# 19-Power-P5V.net
KiCad netlist of a schematic drawn in Altium Designer
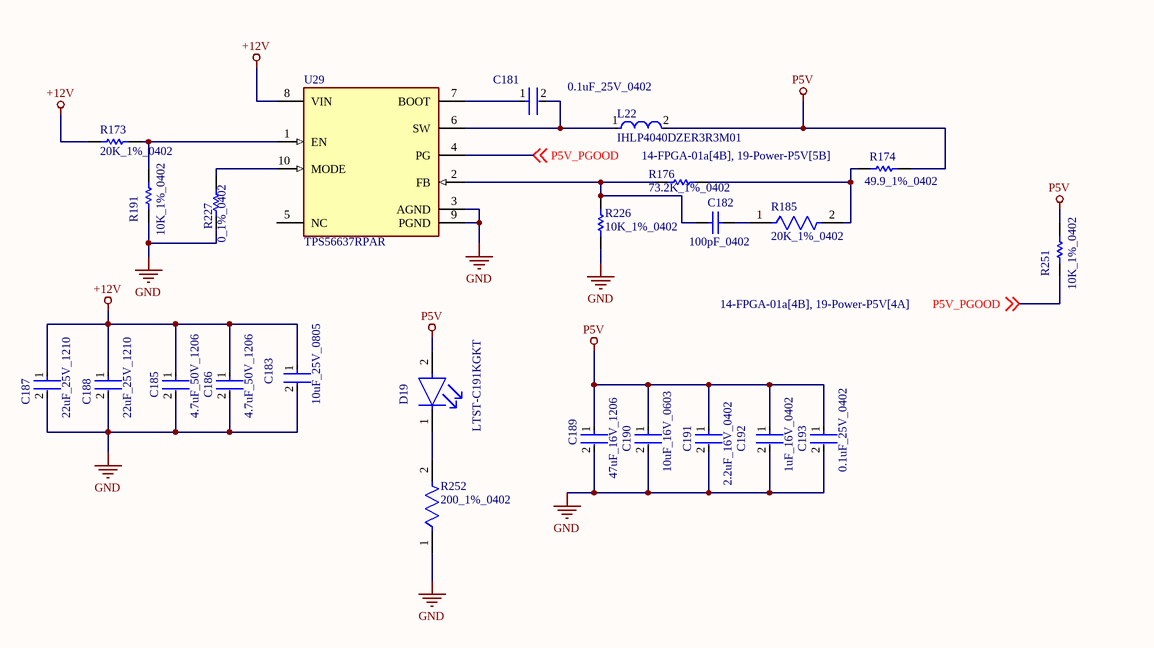
[diagram p0: 19-Power-P5V.SchDoc]

(export (version "E")
  (design (tool "Eeschema 10.0.6"))
  (components
    (comp (ref "C181")
      (value "0.1uF_25V_0402")
      (footprint "FP-0402-L_1_0_1-W_0_5_0_1-IPC_C")
      (description "General Purpose Ceramic Capacitor, 0402, 100nF, 10%, X7R, 15%, 25V")
      (fields (field (name "VOLTAGE") "25V") (field (name "TOLERANCE") "10%"))
      (libsource (lib "Altium Content Vault") (part "b4654b650e69147ec39a6b967a45e02"))
    )
    (comp (ref "C182")
      (value "100pF_0402")
      (footprint "CAPC1005X55X25ML05T10")
      (fields (field (name "MANUFACTURER") "Murata") (field (name "PART NUMBER") "GRM1555C1H101JA01D"))
      (libsource (lib "Altium Content Vault") (part "CAP"))
    )
    (comp (ref "C183")
      (value "10uF_25V_0805")
      (footprint "FP-0805-L_2_0_0_2-W_1_25-MFG")
      (description "Multilayer Ceramic Capacitor 10uF 25V X5R 10% SMD 0805 T/R")
      (fields (field (name "VOLTAGE") "16V") (field (name "TOLERANCE") "10%"))
      (libsource (lib "Altium Content Vault") (part "02cd4be3c70576c341d710602a673aa"))
    )
    (comp (ref "C185")
      (value "4.7uF_50V_1206")
      (footprint "FP-GRM31C-0_2-e0_3_0_8-IPC_C")
      (description "Chip Multilayer Ceramic Capacitors for General Purpose, 1206, 4.7uF, X7R, 15%, 10%, 50V")
      (fields (field (name "VOLTAGE") "50V") (field (name "TOLERANCE") "10%"))
      (libsource (lib "Altium Content Vault") (part "02cd4be3c70576c341d710602a673aa"))
    )
    (comp (ref "C186")
      (value "4.7uF_50V_1206")
      (footprint "FP-GRM31C-0_2-e0_3_0_8-IPC_C")
      (description "Chip Multilayer Ceramic Capacitors for General Purpose, 1206, 4.7uF, X7R, 15%, 10%, 50V")
      (fields (field (name "VOLTAGE") "50V") (field (name "TOLERANCE") "10%"))
      (libsource (lib "Altium Content Vault") (part "02cd4be3c70576c341d710602a673aa"))
    )
    (comp (ref "C187")
      (value "22uF_25V_1210")
      (footprint "FP-MK325M-MFG")
      (description "CAP CER 22UF 25V X5R 1210")
      (fields (field (name "TOLERANCE") "20%"))
      (libsource (lib "Altium Content Vault") (part "b4654b650e69147ec39a6b967a45e02"))
    )
    (comp (ref "C188")
      (value "22uF_25V_1210")
      (footprint "FP-MK325M-MFG")
      (description "CAP CER 22UF 25V X5R 1210")
      (fields (field (name "TOLERANCE") "20%"))
      (libsource (lib "Altium Content Vault") (part "b4654b650e69147ec39a6b967a45e02"))
    )
    (comp (ref "C189")
      (value "47uF_16V_1206")
      (footprint "FP-C3216-160-0_2-MFG")
      (description "Multilayer Ceramic Capacitors 47uF ±20% 16V X5R SMD 1206")
      (fields (field (name "TOLERANCE") "20%"))
      (libsource (lib "Altium Content Vault") (part "11868f565c42a9108669ba33697ecf6"))
    )
    (comp (ref "C190")
      (value "10uF_16V_0603")
      (footprint "FP-0603-L_1_6_0_2-W_0_8_0-MFG")
      (description "Multilayer Ceramic Capacitor 10uF 16V X5R 20% SMD 0603 T/R")
      (fields (field (name "TOLERANCE") "20%"))
      (libsource (lib "Altium Content Vault") (part "b4654b650e69147ec39a6b967a45e02"))
    )
    (comp (ref "C191")
      (value "2.2uF_16V_0402")
      (footprint "FP-C1005-050-0_05-IPC_A")
      (description "Multilayer Ceramic Capacitors 2.2μF ±10% 16V X5R SMD 0402")
      (fields (field (name "TOLERANCE") "10%"))
      (libsource (lib "Altium Content Vault") (part "b4654b650e69147ec39a6b967a45e02"))
    )
    (comp (ref "C192")
      (value "1uF_16V_0402")
      (footprint "FP-0402-L_1_0_0_05-W_0_5-IPC_A")
      (description "None")
      (fields (field (name "TOLERANCE") "10%"))
      (libsource (lib "Altium Content Vault") (part "b4654b650e69147ec39a6b967a45e02"))
    )
    (comp (ref "C193")
      (value "0.1uF_25V_0402")
      (footprint "FP-0402-L_1_0_1-W_0_5_0_1-IPC_C")
      (description "General Purpose Ceramic Capacitor, 0402, 100nF, 10%, X7R, 15%, 25V")
      (fields (field (name "VOLTAGE") "25V") (field (name "TOLERANCE") "10%"))
      (libsource (lib "Altium Content Vault") (part "b4654b650e69147ec39a6b967a45e02"))
    )
    (comp (ref "D19")
      (value "LTST-C191KGKT")
      (footprint "FP-LTST-C191KGKT-MFG")
      (description "LED GREEN CLEAR SMD")
      (libsource (lib "Altium Content Vault") (part "8706943c75ba83719d021d2fdc84c58"))
    )
    (comp (ref "L22")
      (value "IHLP4040DZER3R3M01")
      (footprint "FP-IHLP-4040DZ-FP_3_124x3-MFG")
      (description "Commercial Inductors, High Saturation Series 3.3uH 10A 14.4mΩ 20%")
      (fields (field (name "TOLERANCE") "20%"))
      (libsource (lib "Altium Content Vault") (part "725321dda6339637d4d059423bc1c3c"))
    )
    (comp (ref "R173")
      (value "20K_1%_0402")
      (footprint "RESC1005X40X25NL10T10")
      (fields (field (name "PART NUMBER") "MC00625W0402120K") (field (name "MANUFACTURER") "Multicomp"))
      (libsource (lib "Altium Content Vault") (part "RES"))
    )
    (comp (ref "R174")
      (value "49.9_1%_0402")
      (footprint "RESC1005X40X25LL05T10")
      (fields (field (name "MANUFACTURER") "Yageo / Phycomp") (field (name "PART NUMBER") "RC0402FR-0749R9L"))
      (libsource (lib "Altium Content Vault") (part "RES"))
    )
    (comp (ref "R176")
      (value "73.2K_1%_0402")
      (footprint "RESC1005X40X25LL05T05")
      (fields (field (name "PART NUMBER") "ERJ-2RKF7322X") (field (name "MANUFACTURER") "Panasonic"))
      (libsource (lib "Altium Content Vault") (part "RES"))
    )
    (comp (ref "R185")
      (value "20K_1%_0402")
      (footprint "FP-ERJ2RK-MFG")
      (description "RES SMD 20K OHM 1% 1/10W 0402")
      (fields (field (name "TOLERANCE") "1%"))
      (libsource (lib "Altium Content Vault") (part "1029c3af85768c4190bb7ad29bc67b5"))
    )
    (comp (ref "R191")
      (value "10K_1%_0402")
      (footprint "RESC1005X40X25LL05T05")
      (description "Chip Resistor, 10 KOhm, +/- 1%, 0.1 W, -55 to 155 degC, 0402 (1005 Metric), RoHS, Tape and Reel")
      (fields (field (name "TOLERANCE") "1%") (field (name "MANUFACTURER") "Panasonic"))
      (libsource (lib "Altium Content Vault") (part "RES-2"))
    )
    (comp (ref "R226")
      (value "10K_1%_0402")
      (footprint "RESC1005X40X25LL05T05")
      (description "Chip Resistor, 10 KOhm, +/- 1%, 0.1 W, -55 to 155 degC, 0402 (1005 Metric), RoHS, Tape and Reel")
      (fields (field (name "TOLERANCE") "1%") (field (name "MANUFACTURER") "Panasonic"))
      (libsource (lib "Altium Content Vault") (part "RES-2"))
    )
    (comp (ref "R227")
      (value "0_1%_0402")
      (footprint "RESC1005X40X25LL05T05")
      (description "Chip Resistor, 0 Ohm, 0.1 W, -55 to 155 degC, 0402 (1005 Metric), RoHS, Tape and Reel")
      (fields (field (name "MANUFACTURER") "Panasonic") (field (name "TOLERANCE") "5%"))
      (libsource (lib "Altium Content Vault") (part "RES-2"))
    )
    (comp (ref "R251")
      (value "10K_1%_0402")
      (footprint "RESC1005X40X25LL05T05")
      (description "Chip Resistor, 10 KOhm, +/- 1%, 0.1 W, -55 to 155 degC, 0402 (1005 Metric), RoHS, Tape and Reel")
      (fields (field (name "TOLERANCE") "1%") (field (name "MANUFACTURER") "Panasonic"))
      (libsource (lib "Altium Content Vault") (part "RES-2"))
    )
    (comp (ref "R252")
      (value "200_1%_0402")
      (footprint "FP-ERJ2RK-IPC_A")
      (description "RES SMD 200 OHM 1% 1/10W 0402")
      (fields (field (name "TOLERANCE") "1%"))
      (libsource (lib "Altium Content Vault") (part "1029c3af85768c4190bb7ad29bc67b5"))
    )
    (comp (ref "U29")
      (value "TPS56637RPAR")
      (footprint "FP-RPA0010A-MFG")
      (description "IC POWER MANAGEMENT")
      (fields
        (field (name "OCTOPART") "https://octopart.com/tps56637rpar-texas+instruments-97650653")
        (field (name "MANUFACTURER") "Texas Instruments")
      )
      (libsource (lib "Altium Content Vault") (part "31007e10bcfaaa9b7385bfd54c3e755"))
    )
  )
  (nets
    (net (code "1") (name "+12V") (class "Default")
      (node (ref "C183") (pin "1") (pinfunction "1_1") (pintype "passive"))
      (node (ref "C185") (pin "1") (pinfunction "1_1") (pintype "passive"))
      (node (ref "C186") (pin "1") (pinfunction "1_1") (pintype "passive"))
      (node (ref "C187") (pin "1") (pinfunction "1_1") (pintype "passive"))
      (node (ref "C188") (pin "1") (pinfunction "1_1") (pintype "passive"))
      (node (ref "R173") (pin "1") (pinfunction "1_1") (pintype "passive"))
      (node (ref "U29") (pin "8") (pinfunction "VIN_8") (pintype "power_in"))
    )
    (net (code "2") (name "GND") (class "Default")
      (node (ref "C183") (pin "2") (pinfunction "2_2") (pintype "passive"))
      (node (ref "C185") (pin "2") (pinfunction "2_2") (pintype "passive"))
      (node (ref "C186") (pin "2") (pinfunction "2_2") (pintype "passive"))
      (node (ref "C187") (pin "2") (pinfunction "2_2") (pintype "passive"))
      (node (ref "C188") (pin "2") (pinfunction "2_2") (pintype "passive"))
      (node (ref "C189") (pin "2") (pinfunction "2_2") (pintype "passive"))
      (node (ref "C190") (pin "2") (pinfunction "2_2") (pintype "passive"))
      (node (ref "C191") (pin "2") (pinfunction "2_2") (pintype "passive"))
      (node (ref "C192") (pin "2") (pinfunction "2_2") (pintype "passive"))
      (node (ref "C193") (pin "2") (pinfunction "2_2") (pintype "passive"))
      (node (ref "R191") (pin "1") (pinfunction "1_1") (pintype "passive"))
      (node (ref "R226") (pin "1") (pinfunction "1_1") (pintype "passive"))
      (node (ref "R227") (pin "1") (pinfunction "1_1") (pintype "passive"))
      (node (ref "R252") (pin "1") (pinfunction "1_1") (pintype "passive"))
      (node (ref "U29") (pin "3") (pinfunction "AGND_3") (pintype "power_in"))
      (node (ref "U29") (pin "9") (pinfunction "PGND_9") (pintype "power_in"))
    )
    (net (code "3") (name "Net-(C182-Pad2)") (class "Default")
      (node (ref "C182") (pin "2") (pinfunction "2_2") (pintype "passive"))
      (node (ref "R185") (pin "1") (pinfunction "1_1") (pintype "passive"))
    )
    (net (code "4") (name "Net-(D19-C)") (class "Default")
      (node (ref "D19") (pin "1") (pinfunction "C_1") (pintype "passive"))
      (node (ref "R252") (pin "2") (pinfunction "2_2") (pintype "passive"))
    )
    (net (code "5") (name "Net-(R174-Pad1)") (class "Default")
      (node (ref "R174") (pin "1") (pinfunction "1_1") (pintype "passive"))
      (node (ref "R176") (pin "2") (pinfunction "2_2") (pintype "passive"))
      (node (ref "R185") (pin "2") (pinfunction "2_2") (pintype "passive"))
    )
    (net (code "6") (name "Net-(U29-BOOT)") (class "Default")
      (node (ref "C181") (pin "1") (pinfunction "1_1") (pintype "passive"))
      (node (ref "U29") (pin "7") (pinfunction "BOOT_7") (pintype "power_in"))
    )
    (net (code "7") (name "Net-(U29-EN)") (class "Default")
      (node (ref "R173") (pin "2") (pinfunction "2_2") (pintype "passive"))
      (node (ref "R191") (pin "2") (pinfunction "2_2") (pintype "passive"))
      (node (ref "U29") (pin "1") (pinfunction "EN_1") (pintype "input"))
    )
    (net (code "8") (name "Net-(U29-FB)") (class "Default")
      (node (ref "C182") (pin "1") (pinfunction "1_1") (pintype "passive"))
      (node (ref "R176") (pin "1") (pinfunction "1_1") (pintype "passive"))
      (node (ref "R226") (pin "2") (pinfunction "2_2") (pintype "passive"))
      (node (ref "U29") (pin "2") (pinfunction "FB_2") (pintype "input"))
    )
    (net (code "9") (name "Net-(U29-MODE)") (class "Default")
      (node (ref "R227") (pin "2") (pinfunction "2_2") (pintype "passive"))
      (node (ref "U29") (pin "10") (pinfunction "MODE_10") (pintype "input"))
    )
    (net (code "10") (name "Net-(U29-SW)") (class "Default")
      (node (ref "C181") (pin "2") (pinfunction "2_2") (pintype "passive"))
      (node (ref "L22") (pin "1") (pinfunction "1_1") (pintype "passive"))
      (node (ref "U29") (pin "6") (pinfunction "SW_6") (pintype "power_in"))
    )
    (net (code "11") (name "P5V") (class "Default")
      (node (ref "C189") (pin "1") (pinfunction "1_1") (pintype "passive"))
      (node (ref "C190") (pin "1") (pinfunction "1_1") (pintype "passive"))
      (node (ref "C191") (pin "1") (pinfunction "1_1") (pintype "passive"))
      (node (ref "C192") (pin "1") (pinfunction "1_1") (pintype "passive"))
      (node (ref "C193") (pin "1") (pinfunction "1_1") (pintype "passive"))
      (node (ref "D19") (pin "2") (pinfunction "A_2") (pintype "passive"))
      (node (ref "L22") (pin "2") (pinfunction "2_2") (pintype "passive"))
      (node (ref "R174") (pin "2") (pinfunction "2_2") (pintype "passive"))
      (node (ref "R251") (pin "2") (pinfunction "2_2") (pintype "passive"))
    )
    (net (code "12") (name "P5V_PGOOD") (class "Default")
      (node (ref "R251") (pin "1") (pinfunction "1_1") (pintype "passive"))
      (node (ref "U29") (pin "4") (pinfunction "PG_4") (pintype "open_collector"))
    )
    (net (code "13") (name "unconnected-(U29-NC-Pad5)") (class "Default")
      (node (ref "U29") (pin "5") (pinfunction "NC_5") (pintype "passive"))
    )
  )
)
